# lora_mcu.net
KiCad netlist of a schematic drawn in EAGLE
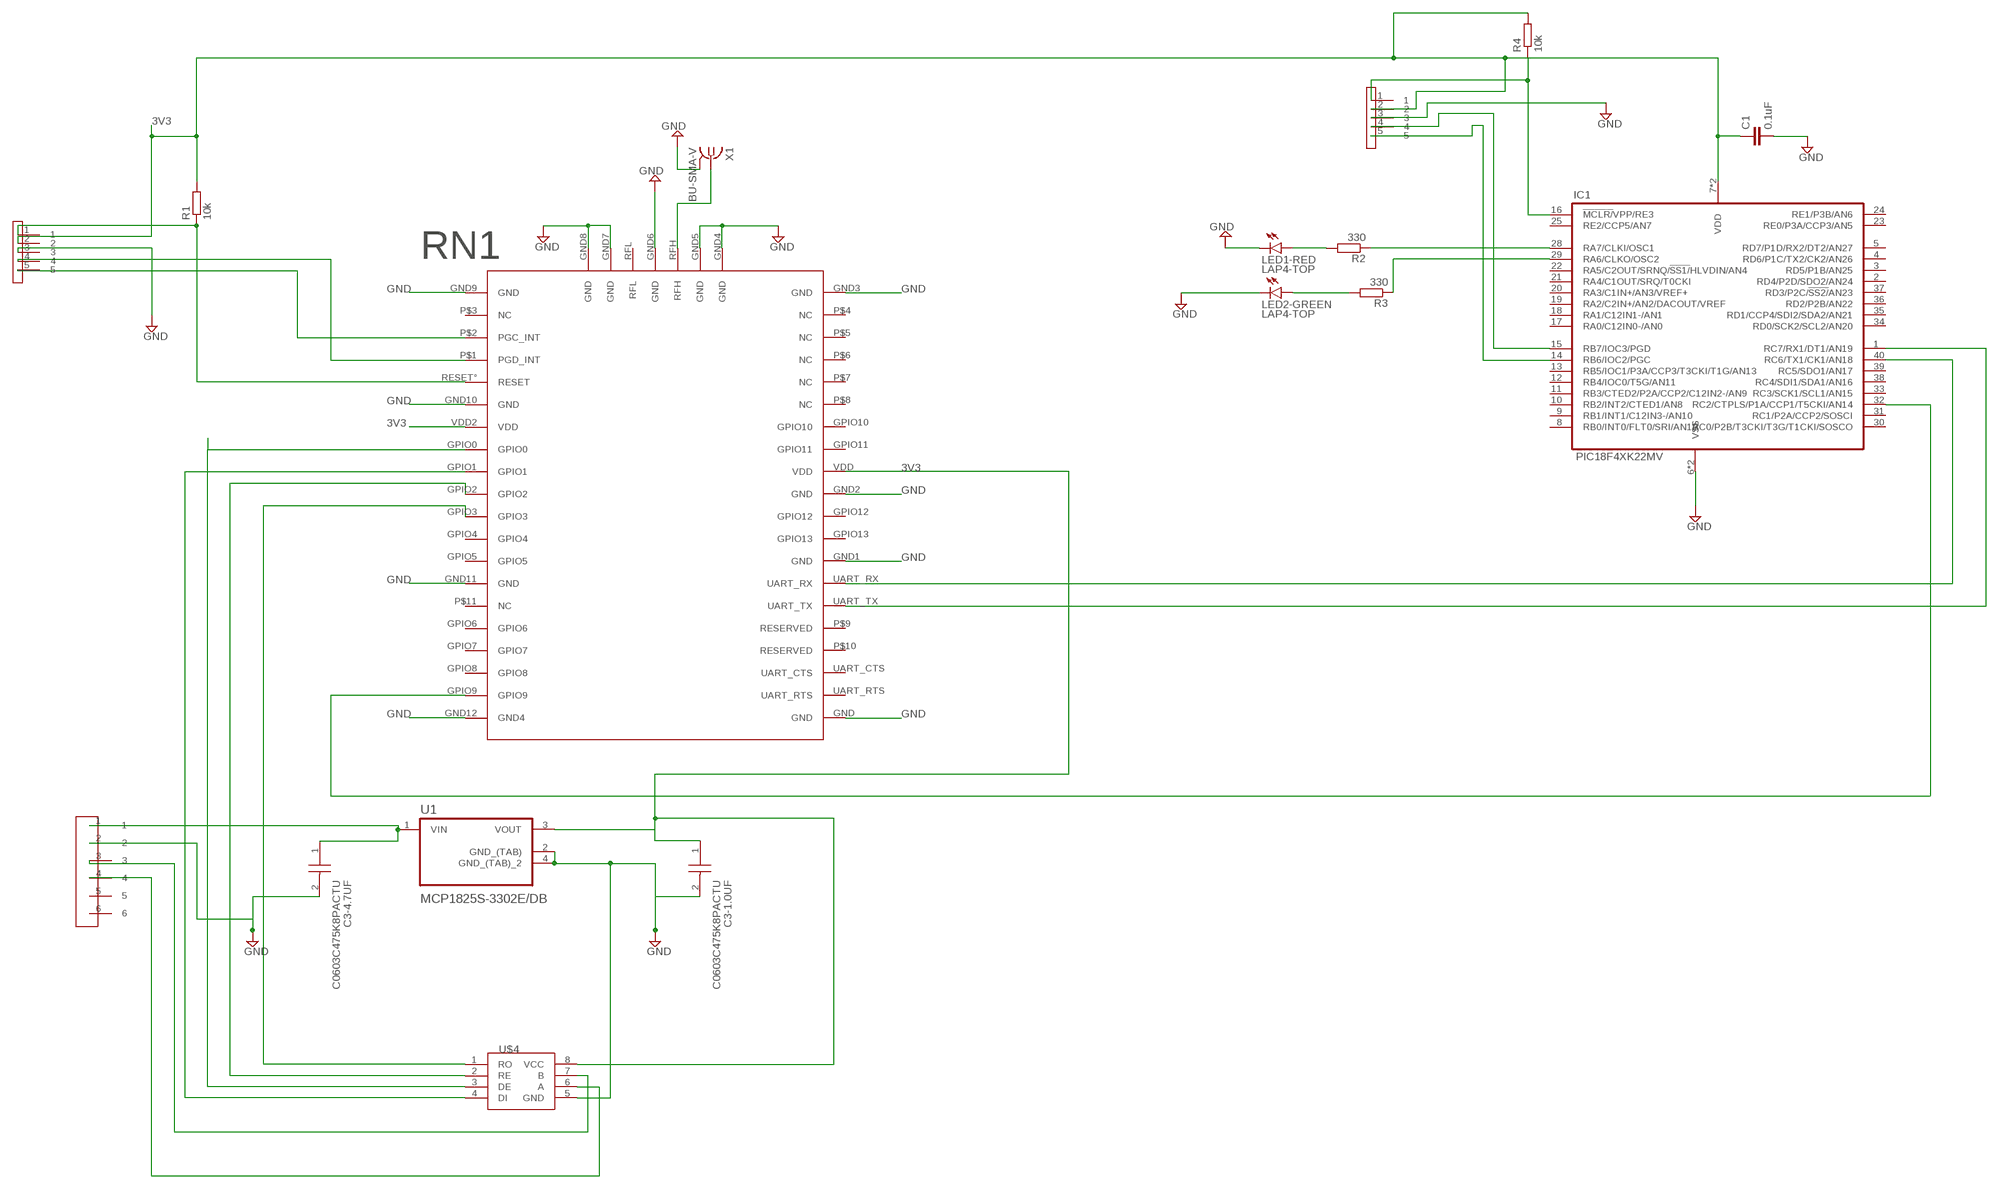
[diagram p0: schematic, sheet 1]

(export (version "E")
  (design (tool "Eeschema 10.0.6"))
  (components
    (comp (ref "C1")
      (value "0.1uF")
      (footprint "eagle-import:C2.5-3")
      (libsource (lib "eagle-import") (part "C2,5-3"))
    )
    (comp (ref "C3-1.0UF")
      (value "C0603C475K8PACTU")
      (footprint "eagle-import:CAPC1608X85N")
      (fields (field (name "MOUSER_PART_NUMBER") "80-C0603C475K8P"))
      (libsource (lib "eagle-import") (part "C0603C475K8PACTU"))
    )
    (comp (ref "C3-4.7UF")
      (value "C0603C475K8PACTU")
      (footprint "eagle-import:CAPC1608X85N")
      (fields (field (name "MOUSER_PART_NUMBER") "80-C0603C475K8P"))
      (libsource (lib "eagle-import") (part "C0603C475K8PACTU"))
    )
    (comp (ref "IC1")
      (value "PIC18F4XK22MV")
      (footprint "eagle-import:UQFN40ML5X5MM")
      (libsource (lib "eagle-import") (part "PIC18F4XK22MV"))
    )
    (comp (ref "LED1-RED")
      (value "LAP4-TOP")
      (footprint "eagle-import:P47F-TOP")
      (libsource (lib "eagle-import") (part "P4-TOPLA"))
    )
    (comp (ref "LED2-GREEN")
      (value "LAP4-TOP")
      (footprint "eagle-import:P47F-TOP")
      (libsource (lib "eagle-import") (part "P4-TOPLA"))
    )
    (comp (ref "R1")
      (value "10k")
      (footprint "eagle-import:R0603")
      (libsource (lib "eagle-import") (part "R-EU_R0603"))
    )
    (comp (ref "R2")
      (value "330")
      (footprint "eagle-import:R0603")
      (libsource (lib "eagle-import") (part "R-EU_R0603"))
    )
    (comp (ref "R3")
      (value "330")
      (footprint "eagle-import:R0603")
      (libsource (lib "eagle-import") (part "R-EU_R0603"))
    )
    (comp (ref "R4")
      (value "10k")
      (footprint "eagle-import:R0603")
      (libsource (lib "eagle-import") (part "R-EU_R0603"))
    )
    (comp (ref "RN1")
      (value "NEW_RN2483")
      (footprint "eagle-import:NEW_RN2483")
      (libsource (lib "eagle-import") (part "NEW_RN2483"))
    )
    (comp (ref "U$1")
      (value "CONNECTOR6")
      (footprint "eagle-import:CONNECTOR6")
      (libsource (lib "eagle-import") (part "CONNECTOR6"))
    )
    (comp (ref "U$2")
      (value "ICSP5")
      (footprint "eagle-import:ICSP")
      (libsource (lib "eagle-import") (part "ICSP5"))
    )
    (comp (ref "U$3")
      (value "ICSP5")
      (footprint "eagle-import:ICSP")
      (libsource (lib "eagle-import") (part "ICSP5"))
    )
    (comp (ref "U$4")
      (value "AMD3485E")
      (footprint "eagle-import:AMD3485E")
      (libsource (lib "eagle-import") (part "AMD3485E"))
    )
    (comp (ref "U1")
      (value "MCP1825S-3302E/DB")
      (footprint "eagle-import:SOT230P700X180-4N")
      (fields (field (name "MF") "Microchip"))
      (libsource (lib "eagle-import") (part "MCP1825S-3302E/DB"))
    )
    (comp (ref "X1")
      (value "BU-SMA-V")
      (footprint "eagle-import:BU-SMA-V")
      (libsource (lib "eagle-import") (part "BU-SMA-V"))
    )
  )
  (nets
    (net (code "1") (name "/3V3") (class "Default")
      (node (ref "C1") (pin "1") (pinfunction "1_1") (pintype "passive"))
      (node (ref "C3-1.0UF") (pin "1") (pinfunction "C1_1") (pintype "bidirectional"))
      (node (ref "IC1") (pin "26") (pinfunction "VDD_26") (pintype "power_in"))
      (node (ref "IC1") (pin "7") (pinfunction "VDD_7") (pintype "power_in"))
      (node (ref "R1") (pin "2") (pinfunction "2_2") (pintype "passive"))
      (node (ref "R4") (pin "2") (pinfunction "2_2") (pintype "passive"))
      (node (ref "RN1") (pin "VDD") (pinfunction "VDD_VDD") (pintype "bidirectional"))
      (node (ref "RN1") (pin "VDD2") (pinfunction "VDD_VDD2") (pintype "bidirectional"))
      (node (ref "U$2") (pin "2") (pinfunction "2_2") (pintype "bidirectional"))
      (node (ref "U$3") (pin "2") (pinfunction "2_2") (pintype "bidirectional"))
      (node (ref "U$4") (pin "8") (pinfunction "VCC_8") (pintype "bidirectional"))
      (node (ref "U1") (pin "3") (pinfunction "VOUT_3") (pintype "output"))
    )
    (net (code "2") (name "GND") (class "Default")
      (node (ref "C1") (pin "2") (pinfunction "2_2") (pintype "passive"))
      (node (ref "C3-1.0UF") (pin "2") (pinfunction "C2_2") (pintype "bidirectional"))
      (node (ref "C3-4.7UF") (pin "2") (pinfunction "C2_2") (pintype "bidirectional"))
      (node (ref "IC1") (pin "27") (pinfunction "VSS_27") (pintype "power_in"))
      (node (ref "IC1") (pin "6") (pinfunction "VSS_6") (pintype "power_in"))
      (node (ref "LED1-RED") (pin "C") (pinfunction "C_C") (pintype "passive"))
      (node (ref "LED2-GREEN") (pin "C") (pinfunction "C_C") (pintype "passive"))
      (node (ref "RN1") (pin "GND") (pinfunction "GND_GND") (pintype "bidirectional"))
      (node (ref "RN1") (pin "GND1") (pinfunction "GND_GND1") (pintype "bidirectional"))
      (node (ref "RN1") (pin "GND10") (pinfunction "GND_GND10") (pintype "bidirectional"))
      (node (ref "RN1") (pin "GND11") (pinfunction "GND_GND11") (pintype "bidirectional"))
      (node (ref "RN1") (pin "GND12") (pinfunction "GND4_GND12") (pintype "bidirectional"))
      (node (ref "RN1") (pin "GND2") (pinfunction "GND_GND2") (pintype "bidirectional"))
      (node (ref "RN1") (pin "GND3") (pinfunction "GND_GND3") (pintype "bidirectional"))
      (node (ref "RN1") (pin "GND4") (pinfunction "GND_GND4") (pintype "bidirectional"))
      (node (ref "RN1") (pin "GND5") (pinfunction "GND_GND5") (pintype "bidirectional"))
      (node (ref "RN1") (pin "GND6") (pinfunction "GND_GND6") (pintype "bidirectional"))
      (node (ref "RN1") (pin "GND7") (pinfunction "GND_GND7") (pintype "bidirectional"))
      (node (ref "RN1") (pin "GND8") (pinfunction "GND_GND8") (pintype "bidirectional"))
      (node (ref "RN1") (pin "GND9") (pinfunction "GND_GND9") (pintype "bidirectional"))
      (node (ref "U$1") (pin "2") (pinfunction "2_2") (pintype "bidirectional"))
      (node (ref "U$2") (pin "3") (pinfunction "3_3") (pintype "bidirectional"))
      (node (ref "U$3") (pin "3") (pinfunction "3_3") (pintype "bidirectional"))
      (node (ref "U$4") (pin "5") (pinfunction "GND_5") (pintype "bidirectional"))
      (node (ref "U1") (pin "2") (pinfunction "GND_(TAB)_2") (pintype "power_in"))
      (node (ref "U1") (pin "4") (pinfunction "GND_(TAB)_2_4") (pintype "power_in"))
      (node (ref "X1") (pin "2") (pinfunction "2_2") (pintype "passive"))
      (node (ref "X1") (pin "3") (pinfunction "2_3") (pintype "passive"))
      (node (ref "X1") (pin "4") (pinfunction "2_4") (pintype "passive"))
      (node (ref "X1") (pin "5") (pinfunction "2_5") (pintype "passive"))
    )
    (net (code "3") (name "Net-(C3-4.7UF-C1)") (class "Default")
      (node (ref "C3-4.7UF") (pin "1") (pinfunction "C1_1") (pintype "bidirectional"))
      (node (ref "U$1") (pin "1") (pinfunction "1_1") (pintype "bidirectional"))
      (node (ref "U1") (pin "1") (pinfunction "VIN_1") (pintype "input"))
    )
    (net (code "4") (name "Net-(IC1-RA6{slash}CLKO{slash}OSC2)") (class "Default")
      (node (ref "IC1") (pin "29") (pinfunction "RA6/CLKO/OSC2_29") (pintype "bidirectional"))
      (node (ref "R3") (pin "1") (pinfunction "1_1") (pintype "passive"))
    )
    (net (code "5") (name "Net-(IC1-RA7{slash}CLKI{slash}OSC1)") (class "Default")
      (node (ref "IC1") (pin "28") (pinfunction "RA7/CLKI/OSC1_28") (pintype "bidirectional"))
      (node (ref "R2") (pin "1") (pinfunction "1_1") (pintype "passive"))
    )
    (net (code "6") (name "Net-(IC1-RB6{slash}IOC2{slash}PGC)") (class "Default")
      (node (ref "IC1") (pin "14") (pinfunction "RB6/IOC2/PGC_14") (pintype "bidirectional"))
      (node (ref "U$3") (pin "5") (pinfunction "5_5") (pintype "bidirectional"))
    )
    (net (code "7") (name "Net-(IC1-RB7{slash}IOC3{slash}PGD)") (class "Default")
      (node (ref "IC1") (pin "15") (pinfunction "RB7/IOC3/PGD_15") (pintype "bidirectional"))
      (node (ref "U$3") (pin "4") (pinfunction "4_4") (pintype "bidirectional"))
    )
    (net (code "8") (name "Net-(IC1-RC2{slash}CTPLS{slash}P1A{slash}CCP1{slash}T5CKI{slash}AN14)") (class "Default")
      (node (ref "IC1") (pin "32") (pinfunction "RC2/CTPLS/P1A/CCP1/T5CKI/AN14_32") (pintype "bidirectional"))
      (node (ref "RN1") (pin "GPIO9") (pinfunction "GPIO9_GPIO9") (pintype "bidirectional"))
    )
    (net (code "9") (name "Net-(IC1-RC6{slash}TX1{slash}CK1{slash}AN18)") (class "Default")
      (node (ref "IC1") (pin "40") (pinfunction "RC6/TX1/CK1/AN18_40") (pintype "bidirectional"))
      (node (ref "RN1") (pin "UART_RX") (pinfunction "UART_RX_UART_RX") (pintype "bidirectional"))
    )
    (net (code "10") (name "Net-(IC1-RC7{slash}RX1{slash}DT1{slash}AN19)") (class "Default")
      (node (ref "IC1") (pin "1") (pinfunction "RC7/RX1/DT1/AN19_1") (pintype "bidirectional"))
      (node (ref "RN1") (pin "UART_TX") (pinfunction "UART_TX_UART_TX") (pintype "bidirectional"))
    )
    (net (code "11") (name "Net-(IC1-~{MCLR{slash}}VPP{slash}RE3)") (class "Default")
      (node (ref "IC1") (pin "16") (pinfunction "~{MCLR/}VPP/RE3_16") (pintype "input"))
      (node (ref "R4") (pin "1") (pinfunction "1_1") (pintype "passive"))
      (node (ref "U$3") (pin "1") (pinfunction "1_1") (pintype "bidirectional"))
    )
    (net (code "12") (name "Net-(LED1-RED-PadA)") (class "Default")
      (node (ref "LED1-RED") (pin "A") (pinfunction "A_A") (pintype "passive"))
      (node (ref "R2") (pin "2") (pinfunction "2_2") (pintype "passive"))
    )
    (net (code "13") (name "Net-(LED2-GREEN-PadA)") (class "Default")
      (node (ref "LED2-GREEN") (pin "A") (pinfunction "A_A") (pintype "passive"))
      (node (ref "R3") (pin "2") (pinfunction "2_2") (pintype "passive"))
    )
    (net (code "14") (name "Net-(RN1-PGC_INT)") (class "Default")
      (node (ref "RN1") (pin "P$2") (pinfunction "PGC_INT_P$2") (pintype "bidirectional"))
      (node (ref "U$2") (pin "5") (pinfunction "5_5") (pintype "bidirectional"))
    )
    (net (code "15") (name "Net-(RN1-PGD_INT)") (class "Default")
      (node (ref "RN1") (pin "P$1") (pinfunction "PGD_INT_P$1") (pintype "bidirectional"))
      (node (ref "U$2") (pin "4") (pinfunction "4_4") (pintype "bidirectional"))
    )
    (net (code "16") (name "Net-(RN1-PadRFH)") (class "Default")
      (node (ref "RN1") (pin "RFH") (pinfunction "RFH_RFH") (pintype "bidirectional"))
      (node (ref "X1") (pin "1") (pinfunction "1_1") (pintype "passive"))
    )
    (net (code "17") (name "Net-(RN1-RESET)") (class "Default")
      (node (ref "R1") (pin "1") (pinfunction "1_1") (pintype "passive"))
      (node (ref "RN1") (pin "RESET°") (pinfunction "RESET_RESET°") (pintype "bidirectional"))
      (node (ref "U$2") (pin "1") (pinfunction "1_1") (pintype "bidirectional"))
    )
    (net (code "18") (name "Net-(U$4-A)") (class "Default")
      (node (ref "U$1") (pin "4") (pinfunction "4_4") (pintype "bidirectional"))
      (node (ref "U$4") (pin "6") (pinfunction "A_6") (pintype "bidirectional"))
    )
    (net (code "19") (name "Net-(U$4-B)") (class "Default")
      (node (ref "U$1") (pin "3") (pinfunction "3_3") (pintype "bidirectional"))
      (node (ref "U$4") (pin "7") (pinfunction "B_7") (pintype "bidirectional"))
    )
    (net (code "20") (name "Net-(U$4-DE)") (class "Default")
      (node (ref "RN1") (pin "GPIO0") (pinfunction "GPIO0_GPIO0") (pintype "bidirectional"))
      (node (ref "U$4") (pin "3") (pinfunction "DE_3") (pintype "bidirectional"))
    )
    (net (code "21") (name "Net-(U$4-DI)") (class "Default")
      (node (ref "RN1") (pin "GPIO1") (pinfunction "GPIO1_GPIO1") (pintype "bidirectional"))
      (node (ref "U$4") (pin "4") (pinfunction "DI_4") (pintype "bidirectional"))
    )
    (net (code "22") (name "Net-(U$4-RE)") (class "Default")
      (node (ref "RN1") (pin "GPIO2") (pinfunction "GPIO2_GPIO2") (pintype "bidirectional"))
      (node (ref "U$4") (pin "2") (pinfunction "RE_2") (pintype "bidirectional"))
    )
    (net (code "23") (name "Net-(U$4-RO)") (class "Default")
      (node (ref "RN1") (pin "GPIO3") (pinfunction "GPIO3_GPIO3") (pintype "bidirectional"))
      (node (ref "U$4") (pin "1") (pinfunction "RO_1") (pintype "bidirectional"))
    )
    (net (code "24") (name "unconnected-(IC1-RA0{slash}C12IN0-{slash}AN0-Pad17)") (class "Default")
      (node (ref "IC1") (pin "17") (pinfunction "RA0/C12IN0-/AN0_17") (pintype "bidirectional"))
    )
    (net (code "25") (name "unconnected-(IC1-RA1{slash}C12IN1-{slash}AN1-Pad18)") (class "Default")
      (node (ref "IC1") (pin "18") (pinfunction "RA1/C12IN1-/AN1_18") (pintype "bidirectional"))
    )
    (net (code "26") (name "unconnected-(IC1-RA2{slash}C2IN+{slash}AN2{slash}DACOUT{slash}VREF-Pad19)") (class "Default")
      (node (ref "IC1") (pin "19") (pinfunction "RA2/C2IN+/AN2/DACOUT/VREF_19") (pintype "bidirectional"))
    )
    (net (code "27") (name "unconnected-(IC1-RA3{slash}C1IN+{slash}AN3{slash}VREF+-Pad20)") (class "Default")
      (node (ref "IC1") (pin "20") (pinfunction "RA3/C1IN+/AN3/VREF+_20") (pintype "bidirectional"))
    )
    (net (code "28") (name "unconnected-(IC1-RA4{slash}C1OUT{slash}SRQ{slash}T0CKI-Pad21)") (class "Default")
      (node (ref "IC1") (pin "21") (pinfunction "RA4/C1OUT/SRQ/T0CKI_21") (pintype "bidirectional"))
    )
    (net (code "29") (name "unconnected-(IC1-RA5{slash}C2OUT{slash}SRNQ{slash}~{SS1{slash}}HLVDIN{slash}AN4-Pad22)") (class "Default")
      (node (ref "IC1") (pin "22") (pinfunction "RA5/C2OUT/SRNQ/~{SS1/}HLVDIN/AN4_22") (pintype "bidirectional"))
    )
    (net (code "30") (name "unconnected-(IC1-RB0{slash}INT0{slash}FLT0{slash}SRI{slash}AN12-Pad8)") (class "Default")
      (node (ref "IC1") (pin "8") (pinfunction "RB0/INT0/FLT0/SRI/AN12_8") (pintype "bidirectional"))
    )
    (net (code "31") (name "unconnected-(IC1-RB1{slash}INT1{slash}C12IN3-{slash}AN10-Pad9)") (class "Default")
      (node (ref "IC1") (pin "9") (pinfunction "RB1/INT1/C12IN3-/AN10_9") (pintype "bidirectional"))
    )
    (net (code "32") (name "unconnected-(IC1-RB2{slash}INT2{slash}CTED1{slash}AN8-Pad10)") (class "Default")
      (node (ref "IC1") (pin "10") (pinfunction "RB2/INT2/CTED1/AN8_10") (pintype "bidirectional"))
    )
    (net (code "33") (name "unconnected-(IC1-RB3{slash}CTED2{slash}P2A{slash}CCP2{slash}C12IN2-{slash}AN9-Pad11)") (class "Default")
      (node (ref "IC1") (pin "11") (pinfunction "RB3/CTED2/P2A/CCP2/C12IN2-/AN9_11") (pintype "bidirectional"))
    )
    (net (code "34") (name "unconnected-(IC1-RB4{slash}IOC0{slash}T5G{slash}AN11-Pad12)") (class "Default")
      (node (ref "IC1") (pin "12") (pinfunction "RB4/IOC0/T5G/AN11_12") (pintype "bidirectional"))
    )
    (net (code "35") (name "unconnected-(IC1-RB5{slash}IOC1{slash}P3A{slash}CCP3{slash}T3CKI{slash}T1G{slash}AN13-Pad13)") (class "Default")
      (node (ref "IC1") (pin "13") (pinfunction "RB5/IOC1/P3A/CCP3/T3CKI/T1G/AN13_13") (pintype "bidirectional"))
    )
    (net (code "36") (name "unconnected-(IC1-RC0{slash}P2B{slash}T3CKI{slash}T3G{slash}T1CKI{slash}SOSCO-Pad30)") (class "Default")
      (node (ref "IC1") (pin "30") (pinfunction "RC0/P2B/T3CKI/T3G/T1CKI/SOSCO_30") (pintype "bidirectional"))
    )
    (net (code "37") (name "unconnected-(IC1-RC1{slash}P2A{slash}CCP2{slash}SOSCI-Pad31)") (class "Default")
      (node (ref "IC1") (pin "31") (pinfunction "RC1/P2A/CCP2/SOSCI_31") (pintype "bidirectional"))
    )
    (net (code "38") (name "unconnected-(IC1-RC3{slash}SCK1{slash}SCL1{slash}AN15-Pad33)") (class "Default")
      (node (ref "IC1") (pin "33") (pinfunction "RC3/SCK1/SCL1/AN15_33") (pintype "bidirectional"))
    )
    (net (code "39") (name "unconnected-(IC1-RC4{slash}SDI1{slash}SDA1{slash}AN16-Pad38)") (class "Default")
      (node (ref "IC1") (pin "38") (pinfunction "RC4/SDI1/SDA1/AN16_38") (pintype "bidirectional"))
    )
    (net (code "40") (name "unconnected-(IC1-RC5{slash}SDO1{slash}AN17-Pad39)") (class "Default")
      (node (ref "IC1") (pin "39") (pinfunction "RC5/SDO1/AN17_39") (pintype "bidirectional"))
    )
    (net (code "41") (name "unconnected-(IC1-RD0{slash}SCK2{slash}SCL2{slash}AN20-Pad34)") (class "Default")
      (node (ref "IC1") (pin "34") (pinfunction "RD0/SCK2/SCL2/AN20_34") (pintype "bidirectional"))
    )
    (net (code "42") (name "unconnected-(IC1-RD1{slash}CCP4{slash}SDI2{slash}SDA2{slash}AN21-Pad35)") (class "Default")
      (node (ref "IC1") (pin "35") (pinfunction "RD1/CCP4/SDI2/SDA2/AN21_35") (pintype "bidirectional"))
    )
    (net (code "43") (name "unconnected-(IC1-RD2{slash}P2B{slash}AN22-Pad36)") (class "Default")
      (node (ref "IC1") (pin "36") (pinfunction "RD2/P2B/AN22_36") (pintype "bidirectional"))
    )
    (net (code "44") (name "unconnected-(IC1-RD3{slash}P2C{slash}~{SS2{slash}}AN23-Pad37)") (class "Default")
      (node (ref "IC1") (pin "37") (pinfunction "RD3/P2C/~{SS2/}AN23_37") (pintype "bidirectional"))
    )
    (net (code "45") (name "unconnected-(IC1-RD4{slash}P2D{slash}SDO2{slash}AN24-Pad2)") (class "Default")
      (node (ref "IC1") (pin "2") (pinfunction "RD4/P2D/SDO2/AN24_2") (pintype "bidirectional"))
    )
    (net (code "46") (name "unconnected-(IC1-RD5{slash}P1B{slash}AN25-Pad3)") (class "Default")
      (node (ref "IC1") (pin "3") (pinfunction "RD5/P1B/AN25_3") (pintype "bidirectional"))
    )
    (net (code "47") (name "unconnected-(IC1-RD6{slash}P1C{slash}TX2{slash}CK2{slash}AN26-Pad4)") (class "Default")
      (node (ref "IC1") (pin "4") (pinfunction "RD6/P1C/TX2/CK2/AN26_4") (pintype "bidirectional"))
    )
    (net (code "48") (name "unconnected-(IC1-RD7{slash}P1D{slash}RX2{slash}DT2{slash}AN27-Pad5)") (class "Default")
      (node (ref "IC1") (pin "5") (pinfunction "RD7/P1D/RX2/DT2/AN27_5") (pintype "bidirectional"))
    )
    (net (code "49") (name "unconnected-(IC1-RE0{slash}P3A{slash}CCP3{slash}AN5-Pad23)") (class "Default")
      (node (ref "IC1") (pin "23") (pinfunction "RE0/P3A/CCP3/AN5_23") (pintype "bidirectional"))
    )
    (net (code "50") (name "unconnected-(IC1-RE1{slash}P3B{slash}AN6-Pad24)") (class "Default")
      (node (ref "IC1") (pin "24") (pinfunction "RE1/P3B/AN6_24") (pintype "bidirectional"))
    )
    (net (code "51") (name "unconnected-(IC1-RE2{slash}CCP5{slash}AN7-Pad25)") (class "Default")
      (node (ref "IC1") (pin "25") (pinfunction "RE2/CCP5/AN7_25") (pintype "bidirectional"))
    )
    (net (code "52") (name "unconnected-(RN1-NC-PadP$3)") (class "Default")
      (node (ref "RN1") (pin "P$3") (pinfunction "NC_P$3") (pintype "bidirectional"))
    )
    (net (code "53") (name "unconnected-(RN1-NC-PadP$4)") (class "Default")
      (node (ref "RN1") (pin "P$4") (pinfunction "NC_P$4") (pintype "bidirectional"))
    )
    (net (code "54") (name "unconnected-(RN1-NC-PadP$5)") (class "Default")
      (node (ref "RN1") (pin "P$5") (pinfunction "NC_P$5") (pintype "bidirectional"))
    )
    (net (code "55") (name "unconnected-(RN1-NC-PadP$6)") (class "Default")
      (node (ref "RN1") (pin "P$6") (pinfunction "NC_P$6") (pintype "bidirectional"))
    )
    (net (code "56") (name "unconnected-(RN1-NC-PadP$7)") (class "Default")
      (node (ref "RN1") (pin "P$7") (pinfunction "NC_P$7") (pintype "bidirectional"))
    )
    (net (code "57") (name "unconnected-(RN1-NC-PadP$8)") (class "Default")
      (node (ref "RN1") (pin "P$8") (pinfunction "NC_P$8") (pintype "bidirectional"))
    )
    (net (code "58") (name "unconnected-(RN1-NC-PadP$11)") (class "Default")
      (node (ref "RN1") (pin "P$11") (pinfunction "NC_P$11") (pintype "bidirectional"))
    )
    (net (code "59") (name "unconnected-(RN1-PadGPIO4)") (class "Default")
      (node (ref "RN1") (pin "GPIO4") (pinfunction "GPIO4_GPIO4") (pintype "bidirectional"))
    )
    (net (code "60") (name "unconnected-(RN1-PadGPIO5)") (class "Default")
      (node (ref "RN1") (pin "GPIO5") (pinfunction "GPIO5_GPIO5") (pintype "bidirectional"))
    )
    (net (code "61") (name "unconnected-(RN1-PadGPIO6)") (class "Default")
      (node (ref "RN1") (pin "GPIO6") (pinfunction "GPIO6_GPIO6") (pintype "bidirectional"))
    )
    (net (code "62") (name "unconnected-(RN1-PadGPIO7)") (class "Default")
      (node (ref "RN1") (pin "GPIO7") (pinfunction "GPIO7_GPIO7") (pintype "bidirectional"))
    )
    (net (code "63") (name "unconnected-(RN1-PadGPIO8)") (class "Default")
      (node (ref "RN1") (pin "GPIO8") (pinfunction "GPIO8_GPIO8") (pintype "bidirectional"))
    )
    (net (code "64") (name "unconnected-(RN1-PadGPIO10)") (class "Default")
      (node (ref "RN1") (pin "GPIO10") (pinfunction "GPIO10_GPIO10") (pintype "bidirectional"))
    )
    (net (code "65") (name "unconnected-(RN1-PadGPIO11)") (class "Default")
      (node (ref "RN1") (pin "GPIO11") (pinfunction "GPIO11_GPIO11") (pintype "bidirectional"))
    )
    (net (code "66") (name "unconnected-(RN1-PadGPIO12)") (class "Default")
      (node (ref "RN1") (pin "GPIO12") (pinfunction "GPIO12_GPIO12") (pintype "bidirectional"))
    )
    (net (code "67") (name "unconnected-(RN1-PadGPIO13)") (class "Default")
      (node (ref "RN1") (pin "GPIO13") (pinfunction "GPIO13_GPIO13") (pintype "bidirectional"))
    )
    (net (code "68") (name "unconnected-(RN1-PadRFL)") (class "Default")
      (node (ref "RN1") (pin "RFL") (pinfunction "RFL_RFL") (pintype "bidirectional"))
    )
    (net (code "69") (name "unconnected-(RN1-PadUART_CTS)") (class "Default")
      (node (ref "RN1") (pin "UART_CTS") (pinfunction "UART_CTS_UART_CTS") (pintype "bidirectional"))
    )
    (net (code "70") (name "unconnected-(RN1-PadUART_RTS)") (class "Default")
      (node (ref "RN1") (pin "UART_RTS") (pinfunction "UART_RTS_UART_RTS") (pintype "bidirectional"))
    )
    (net (code "71") (name "unconnected-(RN1-RESERVED-PadP$9)") (class "Default")
      (node (ref "RN1") (pin "P$9") (pinfunction "RESERVED_P$9") (pintype "bidirectional"))
    )
    (net (code "72") (name "unconnected-(RN1-RESERVED-PadP$10)") (class "Default")
      (node (ref "RN1") (pin "P$10") (pinfunction "RESERVED_P$10") (pintype "bidirectional"))
    )
    (net (code "73") (name "unconnected-(U$1-Pad5)") (class "Default")
      (node (ref "U$1") (pin "5") (pinfunction "5_5") (pintype "bidirectional"))
    )
    (net (code "74") (name "unconnected-(U$1-Pad6)") (class "Default")
      (node (ref "U$1") (pin "6") (pinfunction "6_6") (pintype "bidirectional"))
    )
  )
)
